# ESP32-Main.net
KiCad netlist of a schematic drawn in Altium Designer
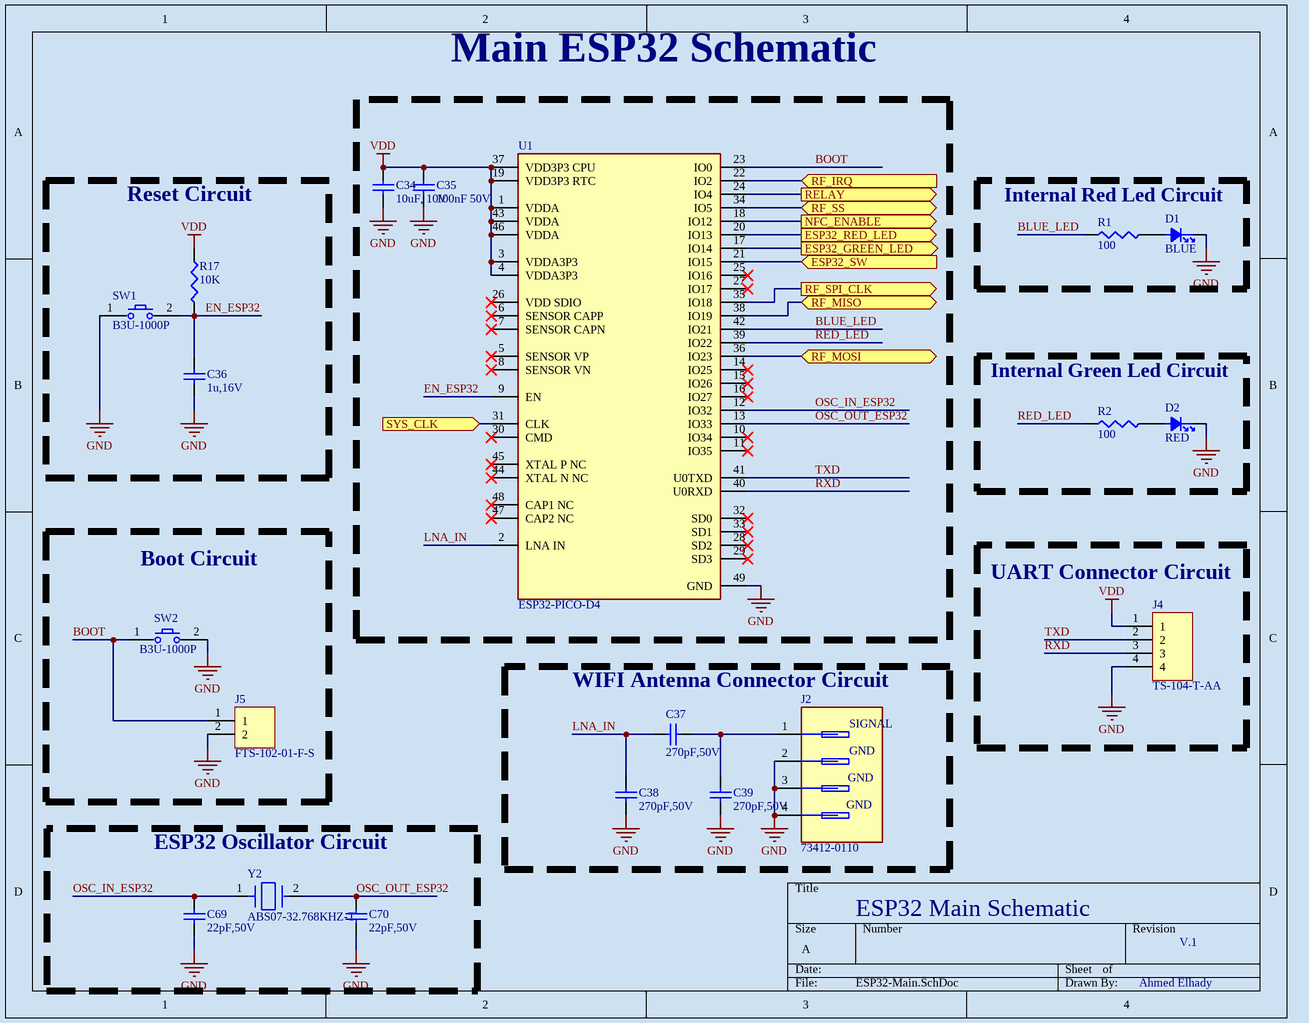
[diagram p0: ESP32-Main.SchDoc]

(export (version "E")
  (design (tool "Eeschema 10.0.6"))
  (components
    (comp (ref "C34")
      (value "10uF, 10V")
      (footprint "CAPC1005X90N")
      (description "10 µF ±20% 10V Ceramic Capacitor X5R 0402 (1005 Metric)")
      (fields
        (field (name "MANUFACTURER") "Samsung Electro-Mechanics")
        (field (name "MANUFACTURER PART NUMBER") "CL05A106MP8NUB8")
      )
      (libsource (lib "Sch for NFC") (part "CL05A106MP8NUB8"))
    )
    (comp (ref "C35")
      (value "100nF 50V")
      (footprint "0603 (1608 Metric)-CAP-100NF-50V")
      (description "0.1 µF ±10% 50V Ceramic Capacitor X7R 0603 (1608 Metric)")
      (fields
        (field (name "MANUFACTURER") "TDK")
        (field (name "MANUFACTURER PART NUMBER") "CGA3E2X7R1H104K080AA")
      )
      (libsource (lib "Sch for NFC") (part "CGA3E2X7R1H104K080AA"))
    )
    (comp (ref "C36")
      (value "1u,16V")
      (footprint "0603 (1608 Metric)-CAP-100NF-50V")
      (description "1 µF ±10% 16V Ceramic Capacitor X7R 0603 (1608 Metric)")
      (fields
        (field (name "MANUFACTURER") "Taiyo Yuden")
        (field (name "MANUFACTURER PART NUMBER") "EMK107B7105KA-T")
      )
      (libsource (lib "Sch for NFC") (part "EMK107B7105KA-T"))
    )
    (comp (ref "C37")
      (value "270pF,50V")
      (footprint "0402_470pF_50VMurata_GCM155-0_05_MFG")
      (description "270 pF ±5% 50V Ceramic Capacitor C0G, NP0 0402 (1005 Metric)")
      (fields
        (field (name "MANUFACTURER") "Murata")
        (field (name "MANUFACTURER PART NUMBER") "GCM1555C1H271JA16D")
      )
      (libsource (lib "Sch for NFC") (part "GCM1555C1H271JA16D"))
    )
    (comp (ref "C38")
      (value "270pF,50V")
      (footprint "0402_470pF_50VMurata_GCM155-0_05_MFG")
      (description "270 pF ±5% 50V Ceramic Capacitor C0G, NP0 0402 (1005 Metric)")
      (fields
        (field (name "MANUFACTURER") "Murata")
        (field (name "MANUFACTURER PART NUMBER") "GCM1555C1H271JA16D")
      )
      (libsource (lib "Sch for NFC") (part "GCM1555C1H271JA16D"))
    )
    (comp (ref "C39")
      (value "270pF,50V")
      (footprint "0402_470pF_50VMurata_GCM155-0_05_MFG")
      (description "270 pF ±5% 50V Ceramic Capacitor C0G, NP0 0402 (1005 Metric)")
      (fields
        (field (name "MANUFACTURER") "Murata")
        (field (name "MANUFACTURER PART NUMBER") "GCM1555C1H271JA16D")
      )
      (libsource (lib "Sch for NFC") (part "GCM1555C1H271JA16D"))
    )
    (comp (ref "C69")
      (value "22pF,50V")
      (footprint "22Pf_50V_Kemet_C0603C220J5GACTU_0")
      (description "22 pF ±5% 50V Ceramic Capacitor C0G, NP0 0603 (1608 Metric)")
      (fields
        (field (name "MANUFACTURER") "KEMET")
        (field (name "MANUFACTURER PART NUMBER") "C0603C220J5GACTU")
      )
      (libsource (lib "Sch for NFC") (part "C0603C220J5GACTU"))
    )
    (comp (ref "C70")
      (value "22pF,50V")
      (footprint "22Pf_50V_Kemet_C0603C220J5GACTU_0")
      (description "22 pF ±5% 50V Ceramic Capacitor C0G, NP0 0603 (1608 Metric)")
      (fields
        (field (name "MANUFACTURER") "KEMET")
        (field (name "MANUFACTURER PART NUMBER") "C0603C220J5GACTU")
      )
      (libsource (lib "Sch for NFC") (part "C0603C220J5GACTU"))
    )
    (comp (ref "D1")
      (value "BLUE")
      (footprint "LED0402B")
      (description "Blue 472nm LED Indication - Discrete 2.8V 0402 (1005 Metric)")
      (fields
        (field (name "MANUFACTURER") "Vishay")
        (field (name "MANUFACTURER PART NUMBER") "VLMB1500-GS08")
      )
      (libsource (lib "Sch for NFC") (part "VLMB1500-GS08"))
    )
    (comp (ref "D2")
      (value "RED")
      (footprint "LED0402R")
      (description "Red 631nm LED Indication - Discrete 2V 0402 (1005 Metric)")
      (fields
        (field (name "MANUFACTURER") "Vishay")
        (field (name "MANUFACTURER PART NUMBER") "VLMS1500-GS08")
      )
      (libsource (lib "Sch for NFC") (part "VLMS1500-GS08"))
    )
    (comp (ref "J2")
      (value "73412-0110")
      (footprint "ANT_CONN_Molex_734-12-0110_0")
      (description "U.FL (UMCC) ANTENNA Connector Receptacle, Male Pin 50 Ohms Surface Mount Solder")
      (fields (field (name "MANUFACTURER") "Molex"))
      (libsource (lib "Sch for NFC") (part "73412-0110"))
    )
    (comp (ref "J4")
      (value "TS-104-T-AA")
      (footprint "4pins-SAMTEC_TS-104-T-AA")
      (description "4 Position Header Connector Post Tin")
      (fields (field (name "MANUFACTURER") "Samtec"))
      (libsource (lib "Sch for NFC") (part "TS-104-T-AA"))
    )
    (comp (ref "J5")
      (value "FTS-102-01-F-S")
      (footprint "HDR1X2_1.27MM")
      (description "Connector Header Through Hole 2 position 0.050\" (1.27mm)")
      (fields (field (name "MANUFACTURER") "Samtec") (field (name "LCSC PART NUMBER") "C6045317"))
      (libsource (lib "Sch for NFC") (part "FTS-102-01-F-S"))
    )
    (comp (ref "R1")
      (value "100")
      (footprint "0603-RES-10OHM-0.1W")
      (description "100 Ohms ±1% 0.125W, 1/8W Chip Resistor 0603 (1608 Metric) Automotive AEC-Q200 Thick Film")
      (fields
        (field (name "MANUFACTURER") "Vishay")
        (field (name "MANUFACTURER PART NUMBER") "CRCW0603100RFKEA")
      )
      (libsource (lib "Sch for NFC") (part "CRCW0603100RFKEA"))
    )
    (comp (ref "R2")
      (value "100")
      (footprint "0603-RES-10OHM-0.1W")
      (description "100 Ohms ±1% 0.125W, 1/8W Chip Resistor 0603 (1608 Metric) Automotive AEC-Q200 Thick Film")
      (fields
        (field (name "MANUFACTURER") "Vishay")
        (field (name "MANUFACTURER PART NUMBER") "CRCW0603100RFKEA")
      )
      (libsource (lib "Sch for NFC") (part "CRCW0603100RFKEA"))
    )
    (comp (ref "R17")
      (value "10K")
      (footprint "YAGEO-0603-10K-0.1W")
      (description "10 kOhms ±1% 0.1W, 1/10W Chip Resistor 0603 (1608 Metric) Moisture Resistant Thick Film")
      (fields
        (field (name "MANUFACTURER") "Yageo Group")
        (field (name "MANUFACTURER PART NUMBER") "RC0603FR-0710KL")
      )
      (libsource (lib "Sch for NFC") (part "RC0603FR-0710KL"))
    )
    (comp (ref "SW1")
      (value "B3U-1000P")
      (footprint "SW_PUSHBOTTON_B3U-1000P")
      (description "Switch Tactile N.O. SPST Round Button Solder Tab 12VDC 50mA 200000Cycles 1.5N SMD Emboss T/R")
      (fields (field (name "MANUFACTURER") "Omron"))
      (libsource (lib "Sch for NFC") (part "B3U-1000P"))
    )
    (comp (ref "SW2")
      (value "B3U-1000P")
      (footprint "SW_PUSHBOTTON_B3U-1000P")
      (description "Switch Tactile N.O. SPST Round Button Solder Tab 12VDC 50mA 200000Cycles 1.5N SMD Emboss T/R")
      (fields (field (name "MANUFACTURER") "Omron"))
      (libsource (lib "Sch for NFC") (part "B3U-1000P"))
    )
    (comp (ref "U1")
      (value "ESP32-PICO-D4")
      (footprint "Espressif_Systems_0_IPC_B")
      (fields (field (name "MANUFACTURER") "Espressif Systems"))
      (libsource (lib "Sch for NFC") (part "ESP32-PICO-D4"))
    )
    (comp (ref "Y2")
      (value "ABS07-32.768KHZ-T")
      (footprint "CRYSTAL_32.768kHZ_FPABS07-MFG")
      (description "32.768 kHz ±20ppm Crystal 12.5pF 70 kOhms 2-SMD, No Lead")
      (fields (field (name "MANUFACTURER") "Abracon") (field (name "TOLERANCE") "0.002%"))
      (libsource (lib "Sch for NFC") (part "ABS07-32.768KHZ-T"))
    )
  )
  (nets
    (net (code "1") (name "/BLUE_LED") (class "Default")
      (node (ref "R1") (pin "1") (pinfunction "1_1") (pintype "passive"))
      (node (ref "U1") (pin "42") (pinfunction "IO21_42") (pintype "passive"))
    )
    (net (code "2") (name "/BOOT") (class "Default")
      (node (ref "J5") (pin "1") (pinfunction "1_1") (pintype "passive"))
      (node (ref "SW2") (pin "1") (pinfunction "1_1") (pintype "passive"))
      (node (ref "U1") (pin "23") (pinfunction "IO0_23") (pintype "passive"))
    )
    (net (code "3") (name "/EN_ESP32") (class "Default")
      (node (ref "C36") (pin "1") (pinfunction "1_1") (pintype "passive"))
      (node (ref "R17") (pin "1") (pinfunction "1_1") (pintype "passive"))
      (node (ref "SW1") (pin "2") (pinfunction "2_2") (pintype "passive"))
      (node (ref "U1") (pin "9") (pinfunction "EN_9") (pintype "passive"))
    )
    (net (code "4") (name "/ESP32_GREEN_LED") (class "Default")
      (node (ref "U1") (pin "17") (pinfunction "IO14_17") (pintype "passive"))
    )
    (net (code "5") (name "/ESP32_RED_LED") (class "Default")
      (node (ref "U1") (pin "20") (pinfunction "IO13_20") (pintype "passive"))
    )
    (net (code "6") (name "/ESP32_SW") (class "Default")
      (node (ref "U1") (pin "21") (pinfunction "IO15_21") (pintype "passive"))
    )
    (net (code "7") (name "/LNA_IN") (class "Default")
      (node (ref "C37") (pin "2") (pinfunction "2_2") (pintype "passive"))
      (node (ref "C38") (pin "2") (pinfunction "2_2") (pintype "passive"))
      (node (ref "U1") (pin "2") (pinfunction "LNA_IN_2") (pintype "passive"))
    )
    (net (code "8") (name "/NFC_ENABLE") (class "Default")
      (node (ref "U1") (pin "18") (pinfunction "IO12_18") (pintype "passive"))
    )
    (net (code "9") (name "/OSC_IN_ESP32") (class "Default")
      (node (ref "C69") (pin "2") (pinfunction "2_2") (pintype "passive"))
      (node (ref "U1") (pin "12") (pinfunction "IO32_12") (pintype "passive"))
      (node (ref "Y2") (pin "1") (pinfunction "1_1") (pintype "passive"))
    )
    (net (code "10") (name "/OSC_OUT_ESP32") (class "Default")
      (node (ref "C70") (pin "2") (pinfunction "2_2") (pintype "passive"))
      (node (ref "U1") (pin "13") (pinfunction "IO33_13") (pintype "passive"))
      (node (ref "Y2") (pin "2") (pinfunction "2_2") (pintype "passive"))
    )
    (net (code "11") (name "/RED_LED") (class "Default")
      (node (ref "R2") (pin "1") (pinfunction "1_1") (pintype "passive"))
      (node (ref "U1") (pin "39") (pinfunction "IO22_39") (pintype "passive"))
    )
    (net (code "12") (name "/RELAY") (class "Default")
      (node (ref "U1") (pin "24") (pinfunction "IO4_24") (pintype "passive"))
    )
    (net (code "13") (name "/RF_IRQ") (class "Default")
      (node (ref "U1") (pin "22") (pinfunction "IO2_22") (pintype "passive"))
    )
    (net (code "14") (name "/RF_MISO") (class "Default")
      (node (ref "U1") (pin "38") (pinfunction "IO19_38") (pintype "passive"))
    )
    (net (code "15") (name "/RF_MOSI") (class "Default")
      (node (ref "U1") (pin "36") (pinfunction "IO23_36") (pintype "passive"))
    )
    (net (code "16") (name "/RF_SPI_CLK") (class "Default")
      (node (ref "U1") (pin "35") (pinfunction "IO18_35") (pintype "passive"))
    )
    (net (code "17") (name "/RF_SS") (class "Default")
      (node (ref "U1") (pin "34") (pinfunction "IO5_34") (pintype "passive"))
    )
    (net (code "18") (name "/RXD") (class "Default")
      (node (ref "J4") (pin "3") (pinfunction "3_3") (pintype "passive"))
      (node (ref "U1") (pin "40") (pinfunction "U0RXD_40") (pintype "passive"))
    )
    (net (code "19") (name "/SYS_CLK") (class "Default")
      (node (ref "U1") (pin "31") (pinfunction "CLK_31") (pintype "passive"))
    )
    (net (code "20") (name "/TXD") (class "Default")
      (node (ref "J4") (pin "2") (pinfunction "2_2") (pintype "passive"))
      (node (ref "U1") (pin "41") (pinfunction "U0TXD_41") (pintype "passive"))
    )
    (net (code "21") (name "GND") (class "Default")
      (node (ref "C34") (pin "1") (pinfunction "1_1") (pintype "passive"))
      (node (ref "C35") (pin "1") (pinfunction "1_1") (pintype "passive"))
      (node (ref "C36") (pin "2") (pinfunction "2_2") (pintype "passive"))
      (node (ref "C38") (pin "1") (pinfunction "1_1") (pintype "passive"))
      (node (ref "C39") (pin "1") (pinfunction "1_1") (pintype "passive"))
      (node (ref "C69") (pin "1") (pinfunction "1_1") (pintype "passive"))
      (node (ref "C70") (pin "1") (pinfunction "1_1") (pintype "passive"))
      (node (ref "D1") (pin "1") (pinfunction "Cathode_1") (pintype "passive"))
      (node (ref "D2") (pin "1") (pinfunction "Cathode_1") (pintype "passive"))
      (node (ref "J2") (pin "2") (pinfunction "GROUND_2") (pintype "passive"))
      (node (ref "J2") (pin "3") (pinfunction "GROUND_3") (pintype "passive"))
      (node (ref "J2") (pin "4") (pinfunction "GROUND_4") (pintype "passive"))
      (node (ref "J4") (pin "4") (pinfunction "4_4") (pintype "passive"))
      (node (ref "J5") (pin "2") (pinfunction "2_2") (pintype "passive"))
      (node (ref "SW1") (pin "1") (pinfunction "1_1") (pintype "passive"))
      (node (ref "SW2") (pin "2") (pinfunction "2_2") (pintype "passive"))
      (node (ref "U1") (pin "49") (pinfunction "GND_49") (pintype "passive"))
    )
    (net (code "22") (name "Net-(D1-Anode)") (class "Default")
      (node (ref "D1") (pin "2") (pinfunction "Anode_2") (pintype "passive"))
      (node (ref "R1") (pin "2") (pinfunction "2_2") (pintype "passive"))
    )
    (net (code "23") (name "Net-(D2-Anode)") (class "Default")
      (node (ref "D2") (pin "2") (pinfunction "Anode_2") (pintype "passive"))
      (node (ref "R2") (pin "2") (pinfunction "2_2") (pintype "passive"))
    )
    (net (code "24") (name "Net-(J2-SIGNAL)") (class "Default")
      (node (ref "C37") (pin "1") (pinfunction "1_1") (pintype "passive"))
      (node (ref "C39") (pin "2") (pinfunction "2_2") (pintype "passive"))
      (node (ref "J2") (pin "1") (pinfunction "SIGNAL_1") (pintype "passive"))
    )
    (net (code "25") (name "VDD") (class "Default")
      (node (ref "C34") (pin "2") (pinfunction "2_2") (pintype "passive"))
      (node (ref "C35") (pin "2") (pinfunction "2_2") (pintype "passive"))
      (node (ref "J4") (pin "1") (pinfunction "1_1") (pintype "passive"))
      (node (ref "R17") (pin "2") (pinfunction "2_2") (pintype "passive"))
      (node (ref "U1") (pin "1") (pinfunction "VDDA_1") (pintype "passive"))
      (node (ref "U1") (pin "19") (pinfunction "VDD3P3_RTC_19") (pintype "passive"))
      (node (ref "U1") (pin "3") (pinfunction "VDDA3P3_3") (pintype "passive"))
      (node (ref "U1") (pin "37") (pinfunction "VDD3P3_CPU_37") (pintype "passive"))
      (node (ref "U1") (pin "4") (pinfunction "VDDA3P3_4") (pintype "passive"))
      (node (ref "U1") (pin "43") (pinfunction "VDDA_43") (pintype "passive"))
      (node (ref "U1") (pin "46") (pinfunction "VDDA_46") (pintype "passive"))
    )
    (net (code "26") (name "unconnected-(U1-CAP1_NC-Pad48)") (class "Default")
      (node (ref "U1") (pin "48") (pinfunction "CAP1_NC_48") (pintype "passive+no_connect"))
    )
    (net (code "27") (name "unconnected-(U1-CAP2_NC-Pad47)") (class "Default")
      (node (ref "U1") (pin "47") (pinfunction "CAP2_NC_47") (pintype "passive+no_connect"))
    )
    (net (code "28") (name "unconnected-(U1-CMD-Pad30)") (class "Default")
      (node (ref "U1") (pin "30") (pinfunction "CMD_30") (pintype "passive+no_connect"))
    )
    (net (code "29") (name "unconnected-(U1-IO16-Pad25)") (class "Default")
      (node (ref "U1") (pin "25") (pinfunction "IO16_25") (pintype "passive+no_connect"))
    )
    (net (code "30") (name "unconnected-(U1-IO17-Pad27)") (class "Default")
      (node (ref "U1") (pin "27") (pinfunction "IO17_27") (pintype "passive+no_connect"))
    )
    (net (code "31") (name "unconnected-(U1-IO25-Pad14)") (class "Default")
      (node (ref "U1") (pin "14") (pinfunction "IO25_14") (pintype "passive+no_connect"))
    )
    (net (code "32") (name "unconnected-(U1-IO26-Pad15)") (class "Default")
      (node (ref "U1") (pin "15") (pinfunction "IO26_15") (pintype "passive+no_connect"))
    )
    (net (code "33") (name "unconnected-(U1-IO27-Pad16)") (class "Default")
      (node (ref "U1") (pin "16") (pinfunction "IO27_16") (pintype "passive+no_connect"))
    )
    (net (code "34") (name "unconnected-(U1-IO34-Pad10)") (class "Default")
      (node (ref "U1") (pin "10") (pinfunction "IO34_10") (pintype "passive+no_connect"))
    )
    (net (code "35") (name "unconnected-(U1-IO35-Pad11)") (class "Default")
      (node (ref "U1") (pin "11") (pinfunction "IO35_11") (pintype "passive+no_connect"))
    )
    (net (code "36") (name "unconnected-(U1-SD0-Pad32)") (class "Default")
      (node (ref "U1") (pin "32") (pinfunction "SD0_32") (pintype "passive+no_connect"))
    )
    (net (code "37") (name "unconnected-(U1-SD1-Pad33)") (class "Default")
      (node (ref "U1") (pin "33") (pinfunction "SD1_33") (pintype "passive+no_connect"))
    )
    (net (code "38") (name "unconnected-(U1-SD2-Pad28)") (class "Default")
      (node (ref "U1") (pin "28") (pinfunction "SD2_28") (pintype "passive+no_connect"))
    )
    (net (code "39") (name "unconnected-(U1-SD3-Pad29)") (class "Default")
      (node (ref "U1") (pin "29") (pinfunction "SD3_29") (pintype "passive+no_connect"))
    )
    (net (code "40") (name "unconnected-(U1-SENSOR_CAPN-Pad7)") (class "Default")
      (node (ref "U1") (pin "7") (pinfunction "SENSOR_CAPN_7") (pintype "passive+no_connect"))
    )
    (net (code "41") (name "unconnected-(U1-SENSOR_CAPP-Pad6)") (class "Default")
      (node (ref "U1") (pin "6") (pinfunction "SENSOR_CAPP_6") (pintype "passive+no_connect"))
    )
    (net (code "42") (name "unconnected-(U1-SENSOR_VN-Pad8)") (class "Default")
      (node (ref "U1") (pin "8") (pinfunction "SENSOR_VN_8") (pintype "passive+no_connect"))
    )
    (net (code "43") (name "unconnected-(U1-SENSOR_VP-Pad5)") (class "Default")
      (node (ref "U1") (pin "5") (pinfunction "SENSOR_VP_5") (pintype "passive+no_connect"))
    )
    (net (code "44") (name "unconnected-(U1-VDD_SDIO-Pad26)") (class "Default")
      (node (ref "U1") (pin "26") (pinfunction "VDD_SDIO_26") (pintype "passive+no_connect"))
    )
    (net (code "45") (name "unconnected-(U1-XTAL_N_NC-Pad44)") (class "Default")
      (node (ref "U1") (pin "44") (pinfunction "XTAL_N_NC_44") (pintype "passive+no_connect"))
    )
    (net (code "46") (name "unconnected-(U1-XTAL_P_NC-Pad45)") (class "Default")
      (node (ref "U1") (pin "45") (pinfunction "XTAL_P_NC_45") (pintype "passive+no_connect"))
    )
  )
)
